# wifi-oil.net
KiCad netlist of a schematic drawn in EAGLE
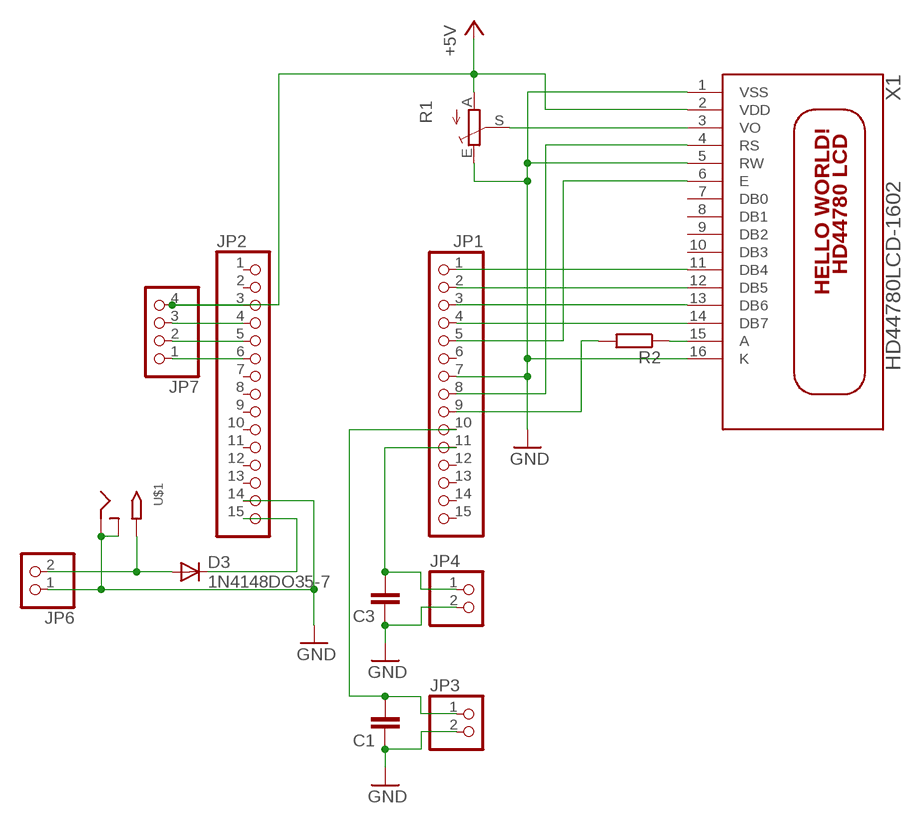
[diagram p0: schematic, sheet 1]

(export (version "E")
  (design (tool "Eeschema 10.0.6"))
  (components
    (comp (ref "C1")
      (value "C-EU025-025X050")
      (footprint "eagle-import:C025-025X050")
      (libsource (lib "eagle-import") (part "C-EU025-025X050"))
    )
    (comp (ref "C3")
      (value "C-EU025-025X050")
      (footprint "eagle-import:C025-025X050")
      (libsource (lib "eagle-import") (part "C-EU025-025X050"))
    )
    (comp (ref "D3")
      (value "1N4148DO35-7")
      (footprint "eagle-import:DO35-7")
      (libsource (lib "eagle-import") (part "1N4148DO35-7"))
    )
    (comp (ref "JP1")
      (value "PINHD-1X15")
      (footprint "eagle-import:1X15")
      (libsource (lib "eagle-import") (part "PINHD-1X15"))
    )
    (comp (ref "JP2")
      (value "PINHD-1X15")
      (footprint "eagle-import:1X15")
      (libsource (lib "eagle-import") (part "PINHD-1X15"))
    )
    (comp (ref "JP3")
      (value "PINHD-1X2")
      (footprint "eagle-import:1X02")
      (libsource (lib "eagle-import") (part "PINHD-1X2"))
    )
    (comp (ref "JP4")
      (value "PINHD-1X2")
      (footprint "eagle-import:1X02")
      (libsource (lib "eagle-import") (part "PINHD-1X2"))
    )
    (comp (ref "JP6")
      (value "PINHD-1X2")
      (footprint "eagle-import:1X02")
      (libsource (lib "eagle-import") (part "PINHD-1X2"))
    )
    (comp (ref "JP7")
      (value "PINHD-1X4")
      (footprint "eagle-import:1X04")
      (libsource (lib "eagle-import") (part "PINHD-1X4"))
    )
    (comp (ref "R1")
      (value "TRIM_EU-RS3")
      (footprint "eagle-import:RS3")
      (libsource (lib "eagle-import") (part "TRIM_EU-RS3"))
    )
    (comp (ref "R2")
      (value "R-EU_0204/7")
      (footprint "eagle-import:0204_7")
      (libsource (lib "eagle-import") (part "R-EU_0204/7"))
    )
    (comp (ref "U$1")
      (value "2.1MMJACKTHM")
      (footprint "eagle-import:PJ-102A")
      (libsource (lib "eagle-import") (part "2.1MMJACKTHM"))
    )
    (comp (ref "X1")
      (value "HD44780LCD-1602")
      (footprint "eagle-import:LCD1602")
      (libsource (lib "eagle-import") (part "HD44780LCD-1602"))
    )
  )
  (nets
    (net (code "1") (name "+5V") (class "Default")
      (node (ref "JP2") (pin "3") (pinfunction "3_3") (pintype "passive"))
      (node (ref "JP7") (pin "4") (pinfunction "4_4") (pintype "passive"))
      (node (ref "R1") (pin "A") (pinfunction "A_A") (pintype "passive"))
      (node (ref "X1") (pin "2") (pinfunction "VDD_2") (pintype "power_in"))
    )
    (net (code "2") (name "GND") (class "Default")
      (node (ref "C1") (pin "1") (pinfunction "1_1") (pintype "passive"))
      (node (ref "C3") (pin "1") (pinfunction "1_1") (pintype "passive"))
      (node (ref "JP1") (pin "7") (pinfunction "7_7") (pintype "passive"))
      (node (ref "JP2") (pin "14") (pinfunction "14_14") (pintype "passive"))
      (node (ref "JP3") (pin "2") (pinfunction "2_2") (pintype "passive"))
      (node (ref "JP4") (pin "2") (pinfunction "2_2") (pintype "passive"))
      (node (ref "JP6") (pin "1") (pinfunction "1_1") (pintype "passive"))
      (node (ref "R1") (pin "E") (pinfunction "E_E") (pintype "passive"))
      (node (ref "U$1") (pin "RING") (pinfunction "RING_RING") (pintype "bidirectional"))
      (node (ref "U$1") (pin "RING_SW") (pinfunction "RING_SW_RING_SW") (pintype "bidirectional"))
      (node (ref "X1") (pin "1") (pinfunction "VSS_1") (pintype "power_in"))
      (node (ref "X1") (pin "16") (pinfunction "K_16") (pintype "input"))
      (node (ref "X1") (pin "5") (pinfunction "RW_5") (pintype "input"))
    )
    (net (code "3") (name "Net-(C1-Pad2)") (class "Default")
      (node (ref "C1") (pin "2") (pinfunction "2_2") (pintype "passive"))
      (node (ref "JP1") (pin "10") (pinfunction "10_10") (pintype "passive"))
      (node (ref "JP3") (pin "1") (pinfunction "1_1") (pintype "passive"))
    )
    (net (code "4") (name "Net-(C3-Pad2)") (class "Default")
      (node (ref "C3") (pin "2") (pinfunction "2_2") (pintype "passive"))
      (node (ref "JP1") (pin "11") (pinfunction "11_11") (pintype "passive"))
      (node (ref "JP4") (pin "1") (pinfunction "1_1") (pintype "passive"))
    )
    (net (code "5") (name "Net-(D3-PadA)") (class "Default")
      (node (ref "D3") (pin "A") (pinfunction "A_A") (pintype "passive"))
      (node (ref "JP6") (pin "2") (pinfunction "2_2") (pintype "passive"))
      (node (ref "U$1") (pin "TIP") (pinfunction "TIP_TIP") (pintype "bidirectional"))
    )
    (net (code "6") (name "Net-(D3-PadC)") (class "Default")
      (node (ref "D3") (pin "C") (pinfunction "C_C") (pintype "passive"))
      (node (ref "JP2") (pin "15") (pinfunction "15_15") (pintype "passive"))
    )
    (net (code "7") (name "Net-(JP1-Pad9)") (class "Default")
      (node (ref "JP1") (pin "9") (pinfunction "9_9") (pintype "passive"))
      (node (ref "R2") (pin "2") (pinfunction "2_2") (pintype "passive"))
    )
    (net (code "8") (name "Net-(JP2-Pad4)") (class "Default")
      (node (ref "JP2") (pin "4") (pinfunction "4_4") (pintype "passive"))
      (node (ref "JP7") (pin "3") (pinfunction "3_3") (pintype "passive"))
    )
    (net (code "9") (name "Net-(JP2-Pad5)") (class "Default")
      (node (ref "JP2") (pin "5") (pinfunction "5_5") (pintype "passive"))
      (node (ref "JP7") (pin "2") (pinfunction "2_2") (pintype "passive"))
    )
    (net (code "10") (name "Net-(JP2-Pad6)") (class "Default")
      (node (ref "JP2") (pin "6") (pinfunction "6_6") (pintype "passive"))
      (node (ref "JP7") (pin "1") (pinfunction "1_1") (pintype "passive"))
    )
    (net (code "11") (name "Net-(X1-A)") (class "Default")
      (node (ref "R2") (pin "1") (pinfunction "1_1") (pintype "passive"))
      (node (ref "X1") (pin "15") (pinfunction "A_15") (pintype "input"))
    )
    (net (code "12") (name "Net-(X1-DB4)") (class "Default")
      (node (ref "JP1") (pin "1") (pinfunction "1_1") (pintype "passive"))
      (node (ref "X1") (pin "11") (pinfunction "DB4_11") (pintype "bidirectional"))
    )
    (net (code "13") (name "Net-(X1-DB5)") (class "Default")
      (node (ref "JP1") (pin "2") (pinfunction "2_2") (pintype "passive"))
      (node (ref "X1") (pin "12") (pinfunction "DB5_12") (pintype "bidirectional"))
    )
    (net (code "14") (name "Net-(X1-DB6)") (class "Default")
      (node (ref "JP1") (pin "3") (pinfunction "3_3") (pintype "passive"))
      (node (ref "X1") (pin "13") (pinfunction "DB6_13") (pintype "bidirectional"))
    )
    (net (code "15") (name "Net-(X1-DB7)") (class "Default")
      (node (ref "JP1") (pin "4") (pinfunction "4_4") (pintype "passive"))
      (node (ref "X1") (pin "14") (pinfunction "DB7_14") (pintype "bidirectional"))
    )
    (net (code "16") (name "Net-(X1-E)") (class "Default")
      (node (ref "JP1") (pin "5") (pinfunction "5_5") (pintype "passive"))
      (node (ref "X1") (pin "6") (pinfunction "E_6") (pintype "input"))
    )
    (net (code "17") (name "Net-(X1-RS)") (class "Default")
      (node (ref "JP1") (pin "8") (pinfunction "8_8") (pintype "passive"))
      (node (ref "X1") (pin "4") (pinfunction "RS_4") (pintype "input"))
    )
    (net (code "18") (name "Net-(X1-VO)") (class "Default")
      (node (ref "R1") (pin "S") (pinfunction "S_S") (pintype "passive"))
      (node (ref "X1") (pin "3") (pinfunction "VO_3") (pintype "input"))
    )
    (net (code "19") (name "unconnected-(JP1-Pad6)") (class "Default")
      (node (ref "JP1") (pin "6") (pinfunction "6_6") (pintype "passive"))
    )
    (net (code "20") (name "unconnected-(JP1-Pad12)") (class "Default")
      (node (ref "JP1") (pin "12") (pinfunction "12_12") (pintype "passive"))
    )
    (net (code "21") (name "unconnected-(JP1-Pad13)") (class "Default")
      (node (ref "JP1") (pin "13") (pinfunction "13_13") (pintype "passive"))
    )
    (net (code "22") (name "unconnected-(JP1-Pad14)") (class "Default")
      (node (ref "JP1") (pin "14") (pinfunction "14_14") (pintype "passive"))
    )
    (net (code "23") (name "unconnected-(JP1-Pad15)") (class "Default")
      (node (ref "JP1") (pin "15") (pinfunction "15_15") (pintype "passive"))
    )
    (net (code "24") (name "unconnected-(JP2-Pad1)") (class "Default")
      (node (ref "JP2") (pin "1") (pinfunction "1_1") (pintype "passive"))
    )
    (net (code "25") (name "unconnected-(JP2-Pad2)") (class "Default")
      (node (ref "JP2") (pin "2") (pinfunction "2_2") (pintype "passive"))
    )
    (net (code "26") (name "unconnected-(JP2-Pad7)") (class "Default")
      (node (ref "JP2") (pin "7") (pinfunction "7_7") (pintype "passive"))
    )
    (net (code "27") (name "unconnected-(JP2-Pad8)") (class "Default")
      (node (ref "JP2") (pin "8") (pinfunction "8_8") (pintype "passive"))
    )
    (net (code "28") (name "unconnected-(JP2-Pad9)") (class "Default")
      (node (ref "JP2") (pin "9") (pinfunction "9_9") (pintype "passive"))
    )
    (net (code "29") (name "unconnected-(JP2-Pad10)") (class "Default")
      (node (ref "JP2") (pin "10") (pinfunction "10_10") (pintype "passive"))
    )
    (net (code "30") (name "unconnected-(JP2-Pad11)") (class "Default")
      (node (ref "JP2") (pin "11") (pinfunction "11_11") (pintype "passive"))
    )
    (net (code "31") (name "unconnected-(JP2-Pad12)") (class "Default")
      (node (ref "JP2") (pin "12") (pinfunction "12_12") (pintype "passive"))
    )
    (net (code "32") (name "unconnected-(JP2-Pad13)") (class "Default")
      (node (ref "JP2") (pin "13") (pinfunction "13_13") (pintype "passive"))
    )
    (net (code "33") (name "unconnected-(X1-DB0-Pad7)") (class "Default")
      (node (ref "X1") (pin "7") (pinfunction "DB0_7") (pintype "bidirectional"))
    )
    (net (code "34") (name "unconnected-(X1-DB1-Pad8)") (class "Default")
      (node (ref "X1") (pin "8") (pinfunction "DB1_8") (pintype "bidirectional"))
    )
    (net (code "35") (name "unconnected-(X1-DB2-Pad9)") (class "Default")
      (node (ref "X1") (pin "9") (pinfunction "DB2_9") (pintype "bidirectional"))
    )
    (net (code "36") (name "unconnected-(X1-DB3-Pad10)") (class "Default")
      (node (ref "X1") (pin "10") (pinfunction "DB3_10") (pintype "bidirectional"))
    )
  )
)
